# cree_module_ye-sheng_kuo_s_conflicted_co.net
KiCad netlist of a schematic drawn in Altium Designer
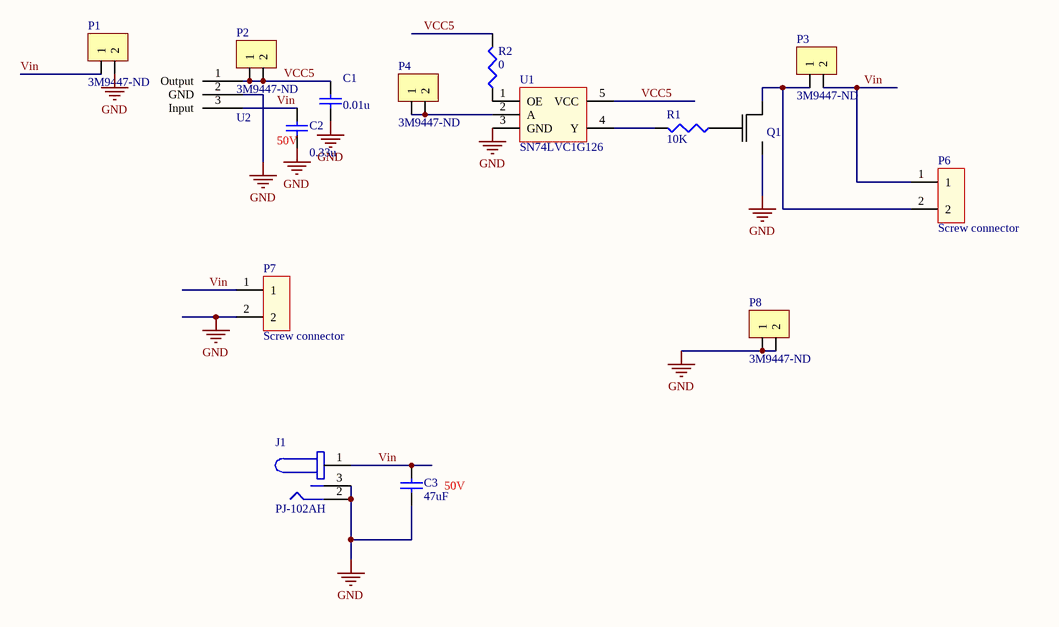
[diagram p0: cree_module (ye-sheng kuo's conflicted copy 2014-07-03).SchDoc]

(export (version "E")
  (design (tool "Eeschema 10.0.6"))
  (components
    (comp (ref "C1")
      (value "0.01u")
      (footprint "1608[0603]")
      (description "Capacitor (Semiconductor SIM Model)")
      (fields (field (name "Comment") "Cap Semi") (field (name "PUBLISHER") "Altium Limited"))
      (libsource (lib "Miscellaneous Devices") (part "Cap Semi"))
    )
    (comp (ref "C2")
      (value "0.33u")
      (footprint "1608[0603]")
      (description "Capacitor (Semiconductor SIM Model)")
      (fields (field (name "Comment") "Cap Semi") (field (name "PUBLISHER") "Altium Limited"))
      (libsource (lib "Miscellaneous Devices") (part "Cap Semi"))
    )
    (comp (ref "C3")
      (value "47uF")
      (footprint "C1210")
      (description "Capacitor (Semiconductor SIM Model)")
      (fields (field (name "Comment") "Cap Semi") (field (name "PUBLISHER") "Altium Limited"))
      (libsource (lib "Miscellaneous Devices") (part "Cap Semi"))
    )
    (comp (ref "J1")
      (value "PJ-102AH")
      (footprint "PJ-102AH")
      (description "CONN PWR JACK 2.1X5.5MM HIGH CUR")
      (libsource (lib "vlc_ctrl") (part "PJ-102AH"))
    )
    (comp (ref "P1")
      (value "1 x 2 header")
      (footprint "1x2 header")
      (description "100 mils standard header")
      (fields (field (name "SUPPLIER PART NUMBER 1") "3M9447-ND"))
      (libsource (lib "vlc_ctrl") (part "1 x 2 header"))
    )
    (comp (ref "P2")
      (value "1 x 2 header")
      (footprint "1x2 header")
      (description "100 mils standard header")
      (fields (field (name "SUPPLIER PART NUMBER 1") "3M9447-ND"))
      (libsource (lib "vlc_ctrl") (part "1 x 2 header"))
    )
    (comp (ref "P3")
      (value "1 x 2 header")
      (footprint "1x2 header")
      (description "100 mils standard header")
      (fields (field (name "SUPPLIER PART NUMBER 1") "3M9447-ND"))
      (libsource (lib "vlc_ctrl") (part "1 x 2 header"))
    )
    (comp (ref "P4")
      (value "1 x 2 header")
      (footprint "1x2 header")
      (description "100 mils standard header")
      (fields (field (name "SUPPLIER PART NUMBER 1") "3M9447-ND"))
      (libsource (lib "vlc_ctrl") (part "1 x 2 header"))
    )
    (comp (ref "P6")
      (value "Screw connector")
      (footprint "MPT_2position")
      (description "Screw connector 2 positions")
      (libsource (lib "vlc_ctrl") (part "MPT_2POS"))
    )
    (comp (ref "P7")
      (value "Screw connector")
      (footprint "MPT_2position")
      (description "Screw connector 2 positions")
      (libsource (lib "vlc_ctrl") (part "MPT_2POS"))
    )
    (comp (ref "P8")
      (value "1 x 2 header")
      (footprint "1x2 header")
      (description "100 mils standard header")
      (fields (field (name "SUPPLIER PART NUMBER 1") "3M9447-ND"))
      (libsource (lib "vlc_ctrl") (part "1 x 2 header"))
    )
    (comp (ref "Q1")
      (value "Si2312CDS")
      (footprint "SOT95P250-3N")
      (description "N-Channel 20 V (D-S) MOSFET")
      (libsource (lib "vlc_ctrl") (part "Si2312CDS"))
    )
    (comp (ref "R1")
      (value "10K")
      (footprint "J1-0603")
      (description "Resistor")
      (fields (field (name "Comment") "Res3") (field (name "PUBLISHER") "Altium Limited"))
      (libsource (lib "Miscellaneous Devices") (part "Res3"))
    )
    (comp (ref "R2")
      (value "0")
      (footprint "J1-0603")
      (description "Resistor")
      (fields (field (name "Comment") "Res3") (field (name "PUBLISHER") "Altium Limited"))
      (libsource (lib "Miscellaneous Devices") (part "Res3"))
    )
    (comp (ref "U1")
      (value "SN74LVC1G126")
      (footprint "SOT23-5")
      (description "Single Bus Buffer Gate With 3-State Output")
      (libsource (lib "vlc_ctrl") (part "SN74LVC1G126"))
    )
    (comp (ref "U2")
      (value "LM78L05")
      (footprint "TO92")
      (description "LM78LXX Series 3-Terminal Positive Regulators")
      (libsource (lib "vlc_ctrl") (part "LM78L05"))
    )
  )
  (nets
    (net (code "1") (name "/VCC5") (class "Default")
      (node (ref "C1") (pin "2") (pinfunction "2_2") (pintype "passive"))
      (node (ref "P2") (pin "1") (pinfunction "1_1") (pintype "passive"))
      (node (ref "P2") (pin "2") (pinfunction "2_2") (pintype "passive"))
      (node (ref "R2") (pin "2") (pinfunction "2_2") (pintype "passive"))
      (node (ref "U1") (pin "5") (pinfunction "VCC_5") (pintype "passive"))
      (node (ref "U2") (pin "1") (pinfunction "Output_1") (pintype "passive"))
    )
    (net (code "2") (name "/Vin") (class "Default")
      (node (ref "C2") (pin "2") (pinfunction "2_2") (pintype "passive"))
      (node (ref "C3") (pin "2") (pinfunction "2_2") (pintype "passive"))
      (node (ref "J1") (pin "1") (pintype "passive"))
      (node (ref "P1") (pin "1") (pinfunction "1_1") (pintype "passive"))
      (node (ref "P3") (pin "2") (pinfunction "2_2") (pintype "passive"))
      (node (ref "P6") (pin "1") (pinfunction "1_1") (pintype "passive"))
      (node (ref "P7") (pin "1") (pinfunction "1_1") (pintype "passive"))
      (node (ref "U2") (pin "3") (pinfunction "Input_3") (pintype "passive"))
    )
    (net (code "3") (name "GND") (class "Default")
      (node (ref "C1") (pin "1") (pinfunction "1_1") (pintype "passive"))
      (node (ref "C2") (pin "1") (pinfunction "1_1") (pintype "passive"))
      (node (ref "C3") (pin "1") (pinfunction "1_1") (pintype "passive"))
      (node (ref "J1") (pin "2") (pintype "passive"))
      (node (ref "J1") (pin "3") (pintype "passive"))
      (node (ref "P1") (pin "2") (pinfunction "2_2") (pintype "passive"))
      (node (ref "P7") (pin "2") (pinfunction "2_2") (pintype "passive"))
      (node (ref "P8") (pin "1") (pinfunction "1_1") (pintype "passive"))
      (node (ref "P8") (pin "2") (pinfunction "2_2") (pintype "passive"))
      (node (ref "Q1") (pin "2") (pinfunction "S_2") (pintype "passive"))
      (node (ref "U1") (pin "3") (pinfunction "GND_3") (pintype "passive"))
      (node (ref "U2") (pin "2") (pinfunction "GND_2") (pintype "passive"))
    )
    (net (code "4") (name "Net-(Q1-D)") (class "Default")
      (node (ref "P3") (pin "1") (pinfunction "1_1") (pintype "passive"))
      (node (ref "P6") (pin "2") (pinfunction "2_2") (pintype "passive"))
      (node (ref "Q1") (pin "3") (pinfunction "D_3") (pintype "passive"))
    )
    (net (code "5") (name "Net-(Q1-G)") (class "Default")
      (node (ref "Q1") (pin "1") (pinfunction "G_1") (pintype "passive"))
      (node (ref "R1") (pin "1") (pinfunction "1_1") (pintype "passive"))
    )
    (net (code "6") (name "Net-(U1-A)") (class "Default")
      (node (ref "P4") (pin "1") (pinfunction "1_1") (pintype "passive"))
      (node (ref "P4") (pin "2") (pinfunction "2_2") (pintype "passive"))
      (node (ref "U1") (pin "2") (pinfunction "A_2") (pintype "passive"))
    )
    (net (code "7") (name "Net-(U1-OE)") (class "Default")
      (node (ref "R2") (pin "1") (pinfunction "1_1") (pintype "passive"))
      (node (ref "U1") (pin "1") (pinfunction "OE_1") (pintype "passive"))
    )
    (net (code "8") (name "Net-(U1-Y)") (class "Default")
      (node (ref "R1") (pin "2") (pinfunction "2_2") (pintype "passive"))
      (node (ref "U1") (pin "4") (pinfunction "Y_4") (pintype "passive"))
    )
  )
)
